# Power_-_Regulation.net
KiCad netlist of a schematic drawn in Altium Designer
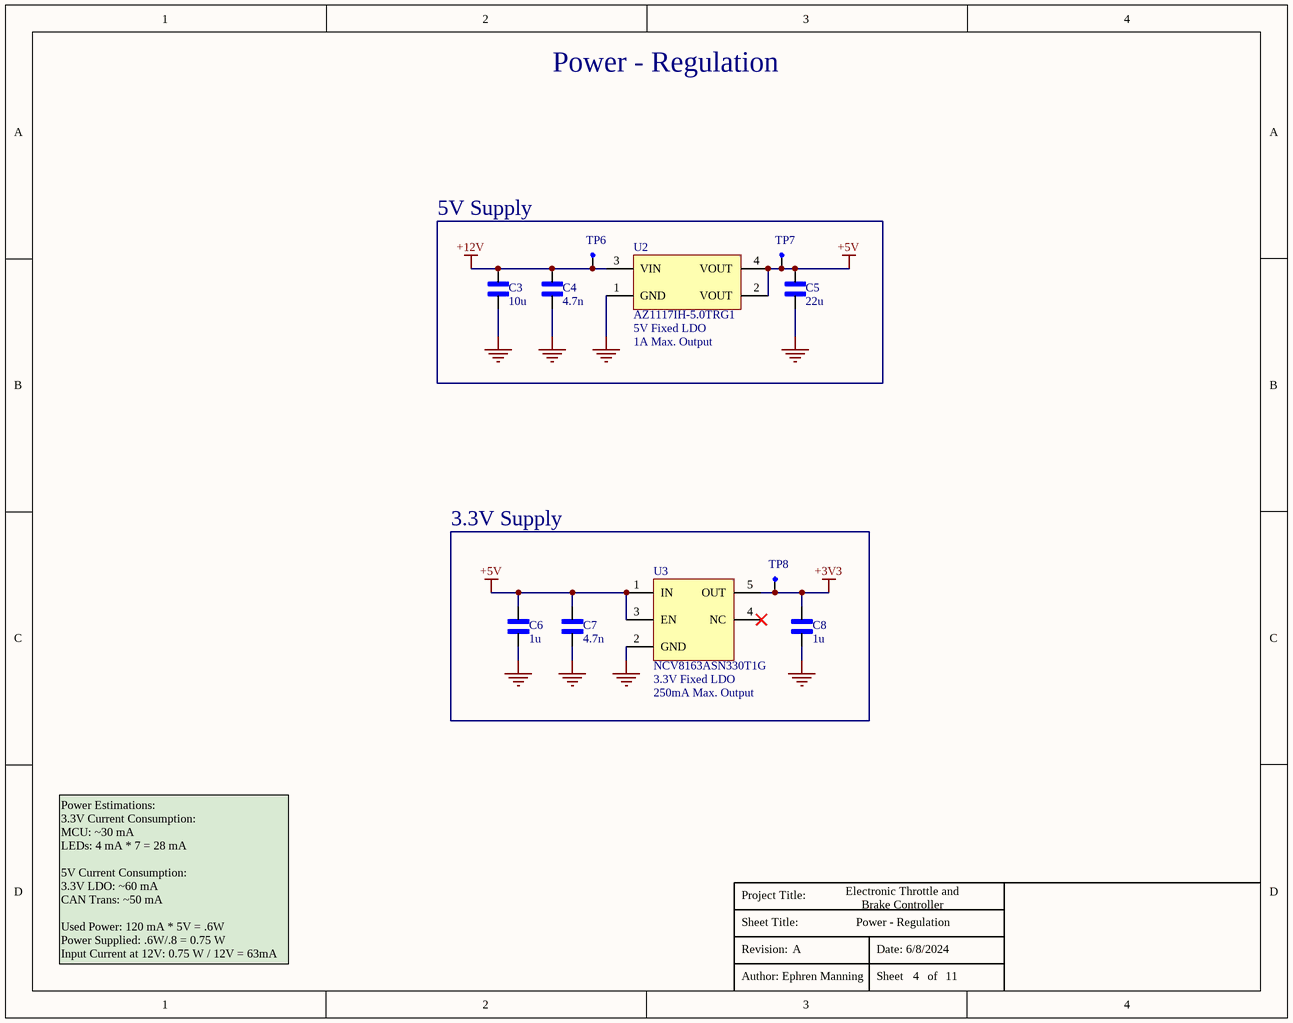
[diagram p0: Power - Regulation.SchDoc]

(export (version "E")
  (design (tool "Eeschema 10.0.6"))
  (components
    (comp (ref "C3")
      (value "10u")
      (footprint "CAP_1210-Footprint-1")
      (description "10uF 35V 10% 1210 MLCC")
      (fields (field (name "DIGIKEY PART NUMBER") "1276-3389-1-ND"))
      (libsource (lib "SAE @ UIC Formula Electric") (part "Capacitor Non-Polarized Symbol"))
    )
    (comp (ref "C4")
      (value "4.7n")
      (footprint "CAP_0402-Footprint-1")
      (description "4.7nF 100V 10% 0402 Ceramic Capacitor")
      (fields (field (name "DIGIKEY PART NUMBER") "490-4765-1-ND"))
      (libsource (lib "SAE @ UIC Formula Electric") (part "CAP_0402-Symbol-1"))
    )
    (comp (ref "C5")
      (value "22u")
      (footprint "CAP_1206-Footprint-1")
      (description "22uF 10V 20% 1206 MLCC")
      (fields (field (name "DIGIKEY PART NUMBER") "1276-3148-1-ND"))
      (libsource (lib "SAE @ UIC Formula Electric") (part "Capacitor Non-Polarized Symbol"))
    )
    (comp (ref "C6")
      (value "1u")
      (footprint "CAP_0805-Footprint-1")
      (description "1uF 25V 10% 0805 MLCC")
      (fields (field (name "DIGIKEY PART NUMBER") "1276-1066-1-ND"))
      (libsource (lib "SAE @ UIC Formula Electric") (part "CAP_0805-Symbol"))
    )
    (comp (ref "C7")
      (value "4.7n")
      (footprint "CAP_0402-Footprint-1")
      (description "4.7nF 100V 10% 0402 Ceramic Capacitor")
      (fields (field (name "DIGIKEY PART NUMBER") "490-4765-1-ND"))
      (libsource (lib "SAE @ UIC Formula Electric") (part "CAP_0402-Symbol-1"))
    )
    (comp (ref "C8")
      (value "1u")
      (footprint "CAP_0805-Footprint-1")
      (description "1uF 25V 10% 0805 MLCC")
      (fields (field (name "DIGIKEY PART NUMBER") "1276-1066-1-ND"))
      (libsource (lib "SAE @ UIC Formula Electric") (part "CAP_0805-Symbol"))
    )
    (comp (ref "TP6")
      (value "SMD Testpoint")
      (footprint "SMD Testpoint-Footprint-1")
      (description "Flat 50x50mil Test Point")
      (libsource (lib "SAE @ UIC Formula Electric") (part "SMD Testpoint-Symbol-1"))
    )
    (comp (ref "TP7")
      (value "SMD Testpoint")
      (footprint "SMD Testpoint-Footprint-1")
      (description "Flat 50x50mil Test Point")
      (libsource (lib "SAE @ UIC Formula Electric") (part "SMD Testpoint-Symbol-1"))
    )
    (comp (ref "TP8")
      (value "SMD Testpoint")
      (footprint "SMD Testpoint-Footprint-1")
      (description "Flat 50x50mil Test Point")
      (libsource (lib "SAE @ UIC Formula Electric") (part "SMD Testpoint-Symbol-1"))
    )
    (comp (ref "U2")
      (value "AZ1117IH-5.0TRG1")
      (footprint "SOT230P700X180-4N")
      (description "5V Fixed Linear Regulator")
      (fields (field (name "DIGIKEY PART NUMBER") "AZ1117IH-5.0TRG1DICT-ND"))
      (libsource (lib "SAE @ UIC Formula Electric") (part "AZ1117IH-5.0TRG1-Symbol-1"))
    )
    (comp (ref "U3")
      (value "NCV8163ASN330T1G")
      (footprint "SOT95P275X110-5N")
      (description "3.3V LDO, Ultra Low Noise 5.5V Max Vin")
      (fields (field (name "DIGIKEY PART NUMBER") "NCV8163ASN330T1GOSCT-ND"))
      (libsource (lib "SAE @ UIC Formula Electric") (part "NCV8163ASN330T1G-Symbol-1"))
    )
  )
  (nets
    (net (code "1") (name "+3V3") (class "Default")
      (node (ref "C8") (pin "2") (pinfunction "2_2") (pintype "passive"))
      (node (ref "TP8") (pin "1") (pinfunction "1_1") (pintype "passive"))
      (node (ref "U3") (pin "5") (pinfunction "OUT_5") (pintype "passive"))
    )
    (net (code "2") (name "+5V") (class "Default")
      (node (ref "C5") (pin "2") (pinfunction "2_2") (pintype "passive"))
      (node (ref "C6") (pin "2") (pinfunction "2_2") (pintype "passive"))
      (node (ref "C7") (pin "2") (pinfunction "2_2") (pintype "passive"))
      (node (ref "TP7") (pin "1") (pinfunction "1_1") (pintype "passive"))
      (node (ref "U2") (pin "2") (pinfunction "VOUT_2") (pintype "passive"))
      (node (ref "U2") (pin "4") (pinfunction "VOUT_4") (pintype "passive"))
      (node (ref "U3") (pin "1") (pinfunction "IN_1") (pintype "passive"))
      (node (ref "U3") (pin "3") (pinfunction "EN_3") (pintype "passive"))
    )
    (net (code "3") (name "+12V") (class "Default")
      (node (ref "C3") (pin "2") (pinfunction "2_2") (pintype "passive"))
      (node (ref "C4") (pin "2") (pinfunction "2_2") (pintype "passive"))
      (node (ref "TP6") (pin "1") (pinfunction "1_1") (pintype "passive"))
      (node (ref "U2") (pin "3") (pinfunction "VIN_3") (pintype "passive"))
    )
    (net (code "4") (name "GND") (class "Default")
      (node (ref "C3") (pin "1") (pinfunction "1_1") (pintype "passive"))
      (node (ref "C4") (pin "1") (pinfunction "1_1") (pintype "passive"))
      (node (ref "C5") (pin "1") (pinfunction "1_1") (pintype "passive"))
      (node (ref "C6") (pin "1") (pinfunction "1_1") (pintype "passive"))
      (node (ref "C7") (pin "1") (pinfunction "1_1") (pintype "passive"))
      (node (ref "C8") (pin "1") (pinfunction "1_1") (pintype "passive"))
      (node (ref "U2") (pin "1") (pinfunction "GND_1") (pintype "passive"))
      (node (ref "U3") (pin "2") (pinfunction "GND_2") (pintype "passive"))
    )
    (net (code "5") (name "unconnected-(U3-NC-Pad4)") (class "Default")
      (node (ref "U3") (pin "4") (pinfunction "NC_4") (pintype "passive+no_connect"))
    )
  )
)
